# Teensy4-CANTool-Rev2.net
KiCad netlist of a schematic drawn in Altium Designer
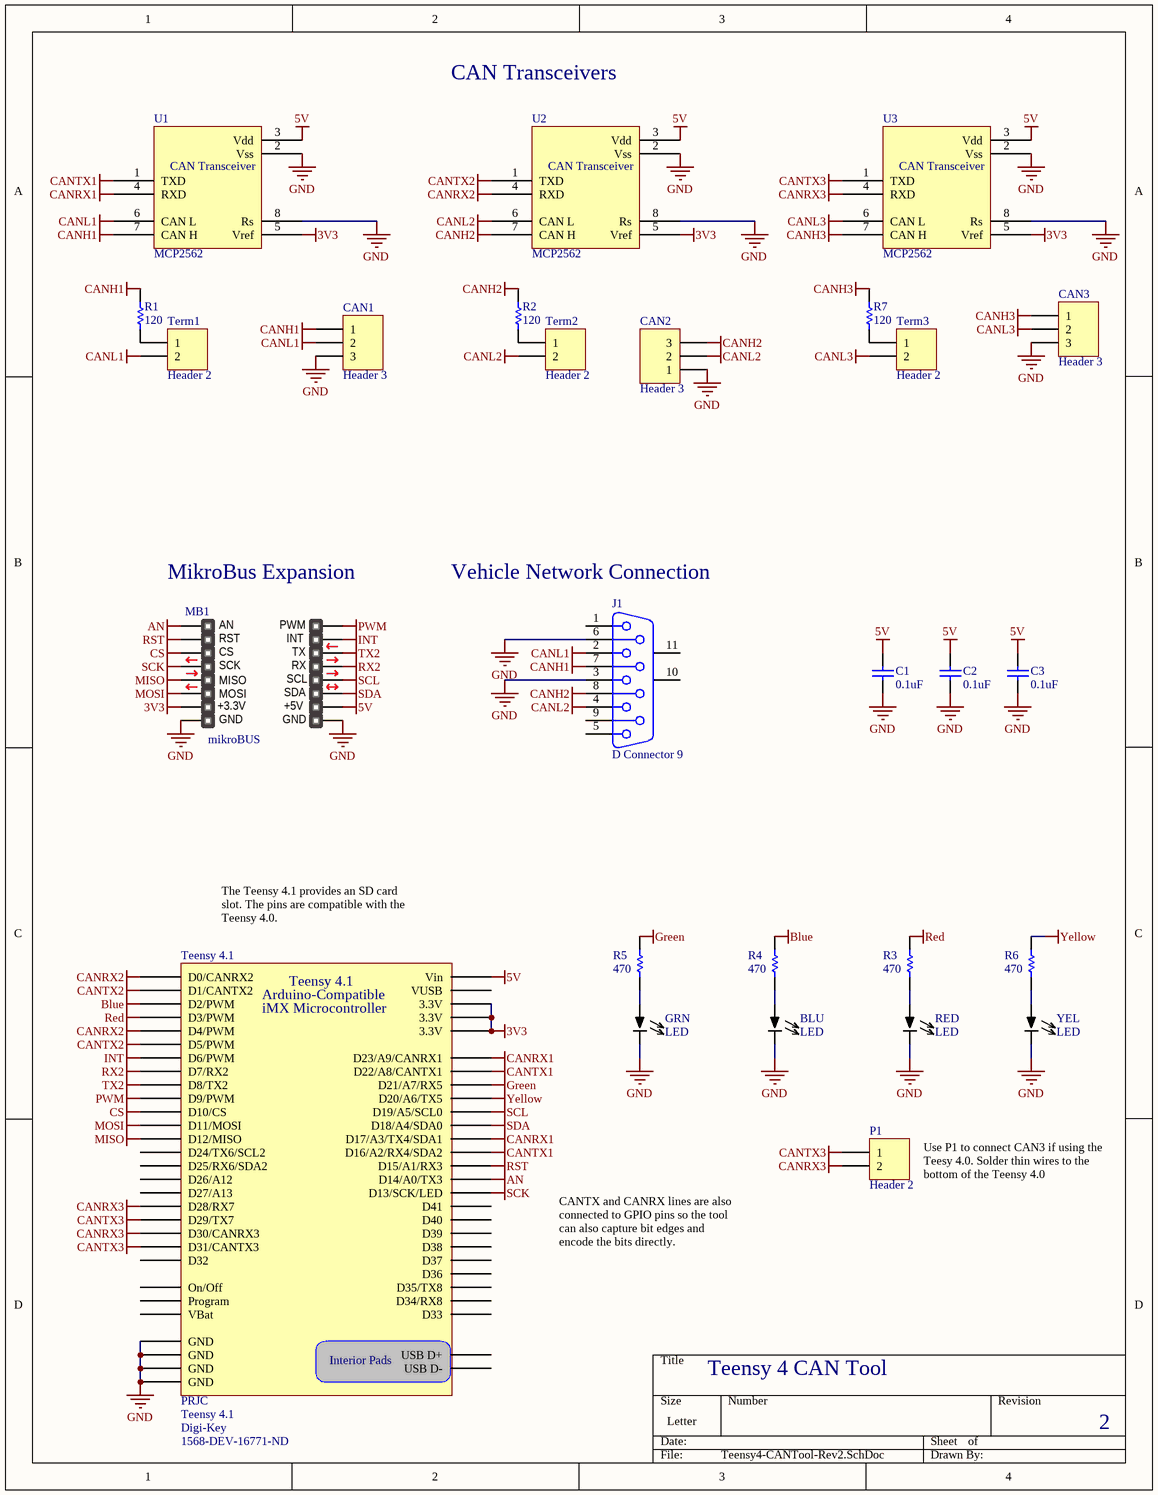
[diagram p0: Teensy4-CANTool-Rev2.SchDoc]

(export (version "E")
  (design (tool "Eeschema 10.0.6"))
  (components
    (comp (ref "BLU")
      (value "LED")
      (footprint "LED - 5mm Through Hole")
      (description "Blue 470nm LED Indication - Discrete 3.2V Radial")
      (fields (field (name "MANUFACTURER") "Würth Elektronik") (field (name "PARTNUMBER") "151051BS04000"))
      (libsource (lib "Custom Parts") (part "LED"))
    )
    (comp (ref "C1")
      (value "0.1uF")
      (footprint "CAPR5-4X5")
      (description "0.1µF ±10% 50V Ceramic Capacitor X7R 0603 (1608 Metric)")
      (fields
        (field (name "MANUFACTURER") "Vishay Beyschlag/Draloric/BC Components")
        (field (name "PARTNUMBER") "K104K15X7RF53H5")
      )
      (libsource (lib "SSS Schematic Library") (part "Cap"))
    )
    (comp (ref "C2")
      (value "0.1uF")
      (footprint "CAPR5-4X5")
      (description "0.1µF ±10% 50V Ceramic Capacitor X7R 0603 (1608 Metric)")
      (fields
        (field (name "MANUFACTURER") "Vishay Beyschlag/Draloric/BC Components")
        (field (name "PARTNUMBER") "K104K15X7RF53H5")
      )
      (libsource (lib "SSS Schematic Library") (part "Cap"))
    )
    (comp (ref "C3")
      (value "0.1uF")
      (footprint "CAPR5-4X5")
      (description "0.1µF ±10% 50V Ceramic Capacitor X7R 0603 (1608 Metric)")
      (fields
        (field (name "MANUFACTURER") "Vishay Beyschlag/Draloric/BC Components")
        (field (name "PARTNUMBER") "K104K15X7RF53H5")
      )
      (libsource (lib "SSS Schematic Library") (part "Cap"))
    )
    (comp (ref "CAN1")
      (value "Header 3")
      (footprint "PCB Terminal Block - 3")
      (description "Header, 3-Pin")
      (fields (field (name "MANUFACTURER") "Phoenix Contact") (field (name "PARTNUMBER") "1935174"))
      (libsource (lib "Miscellaneous Connectors") (part "Header 3"))
    )
    (comp (ref "CAN2")
      (value "Header 3")
      (footprint "PCB Terminal Block - 3")
      (description "Header, 3-Pin")
      (fields (field (name "MANUFACTURER") "Phoenix Contact") (field (name "PARTNUMBER") "1935174"))
      (libsource (lib "") (part "Header 3_1"))
    )
    (comp (ref "CAN3")
      (value "Header 3")
      (footprint "PCB Terminal Block - 3")
      (description "Header, 3-Pin")
      (fields (field (name "MANUFACTURER") "Phoenix Contact") (field (name "PARTNUMBER") "1935174"))
      (libsource (lib "Miscellaneous Connectors") (part "Header 3"))
    )
    (comp (ref "GRN")
      (value "LED")
      (footprint "LED - 5mm Through Hole")
      (description "Green 572nm LED Indication - Discrete 2.1V Radial")
      (fields (field (name "MANUFACTURER") "Würth Elektronik") (field (name "PARTNUMBER") "151051VS04000"))
      (libsource (lib "Custom Parts") (part "LED"))
    )
    (comp (ref "J1")
      (value "D Connector 9")
      (footprint "DSUB1.385-2H9")
      (description "CONN D-SUB PLUG 9POS R/A SLDR")
      (fields
        (field (name "MANUFACTURER") "Assmann WSW Components")
        (field (name "PARTNUMBER") "A-DS 09 A/KG-T2S")
      )
      (libsource (lib "Miscellaneous Connectors") (part "D Connector 9"))
    )
    (comp (ref "MB1")
      (value "mikroBUS")
      (footprint "mikroBUS - Midi")
      (description "mikroBUS compatible add-on board")
      (libsource (lib "mikroBUS_Add-on_standard") (part "mikroBUS compatible add-on board"))
    )
    (comp (ref "P1")
      (value "Header 2")
      (footprint "HDR1X2")
      (description "Header, 2-Pin")
      (libsource (lib "Miscellaneous Connectors") (part "Header 2"))
    )
    (comp (ref "R1")
      (value "120")
      (footprint "AXIAL-0.4")
      (description "120 Ohms ±5% 0.25W, 1/4W Through Hole Resistor Axial Carbon Film")
      (fields (field (name "MANUFACTURER") "YAGEO") (field (name "PARTNUMBER") "CFR-25JB-52-120R"))
      (libsource (lib "Miscellaneous Devices") (part "Res1"))
    )
    (comp (ref "R2")
      (value "120")
      (footprint "AXIAL-0.4")
      (description "120 Ohms ±5% 0.25W, 1/4W Through Hole Resistor Axial Carbon Film")
      (fields (field (name "MANUFACTURER") "YAGEO") (field (name "PARTNUMBER") "CFR-25JB-52-120R"))
      (libsource (lib "Miscellaneous Devices") (part "Res1"))
    )
    (comp (ref "R3")
      (value "470")
      (footprint "AXIAL-0.4")
      (description "470 Ohms ±5% 0.25W, 1/4W Through Hole Resistor Axial Carbon Film")
      (fields (field (name "MANUFACTURER") "YAGEO") (field (name "PARTNUMBER") "CFR-25JB-52-470R"))
      (libsource (lib "Miscellaneous Devices") (part "Res1"))
    )
    (comp (ref "R4")
      (value "470")
      (footprint "AXIAL-0.4")
      (description "470 Ohms ±5% 0.25W, 1/4W Through Hole Resistor Axial Carbon Film")
      (fields (field (name "MANUFACTURER") "YAGEO") (field (name "PARTNUMBER") "CFR-25JB-52-470R"))
      (libsource (lib "Miscellaneous Devices") (part "Res1"))
    )
    (comp (ref "R5")
      (value "470")
      (footprint "AXIAL-0.4")
      (description "470 Ohms ±5% 0.25W, 1/4W Through Hole Resistor Axial Carbon Film")
      (fields (field (name "MANUFACTURER") "YAGEO") (field (name "PARTNUMBER") "CFR-25JB-52-470R"))
      (libsource (lib "Miscellaneous Devices") (part "Res1"))
    )
    (comp (ref "R6")
      (value "470")
      (footprint "AXIAL-0.4")
      (description "470 Ohms ±5% 0.25W, 1/4W Through Hole Resistor Axial Carbon Film")
      (fields (field (name "MANUFACTURER") "YAGEO") (field (name "PARTNUMBER") "CFR-25JB-52-470R"))
      (libsource (lib "Miscellaneous Devices") (part "Res1"))
    )
    (comp (ref "R7")
      (value "120")
      (footprint "AXIAL-0.4")
      (description "120 Ohms ±5% 0.25W, 1/4W Through Hole Resistor Axial Carbon Film")
      (fields (field (name "MANUFACTURER") "YAGEO") (field (name "PARTNUMBER") "CFR-25JB-52-120R"))
      (libsource (lib "Miscellaneous Devices") (part "Res1"))
    )
    (comp (ref "RED")
      (value "LED")
      (footprint "LED - 5mm Through Hole")
      (description "Red 645nm LED Indication - Discrete 2.1V Radial")
      (fields (field (name "MANUFACTURER") "Würth Elektronik") (field (name "PARTNUMBER") "151051RS11000"))
      (libsource (lib "Custom Parts") (part "LED"))
    )
    (comp (ref "Teensy 4.1")
      (value "Teensy 4.1")
      (footprint "Teensy 4.1")
      (description "32 Bit Arduino-Compatible iMX Microcontroller")
      (fields
        (field (name "MANUFACTURER") "PRJC")
        (field (name "PARTNUMBER") "Teensy 4.1")
        (field (name "SUPPLIER 1") "Digi-Key")
        (field (name "SUPPLIER PART NUMBER 1") "1568-DEV-16771-ND")
      )
      (libsource (lib "Teensy") (part "Teensy 4.1"))
    )
    (comp (ref "Term1")
      (value "Header 2")
      (footprint "HDR1X2")
      (description "2 (1 x 2) Position Shunt Connector Open Top, Grip 0.100\" (2.54mm) Gold")
      (fields
        (field (name "MANUFACTURER") "Sullins Connector Solutions")
        (field (name "PARTNUMBER") "NPC02SXON-RC")
      )
      (libsource (lib "Miscellaneous Connectors") (part "Header 2"))
    )
    (comp (ref "Term2")
      (value "Header 2")
      (footprint "HDR1X2")
      (description "2 (1 x 2) Position Shunt Connector Open Top, Grip 0.100\" (2.54mm) Gold")
      (fields
        (field (name "MANUFACTURER") "Sullins Connector Solutions")
        (field (name "PARTNUMBER") "NPC02SXON-RC")
      )
      (libsource (lib "Miscellaneous Connectors") (part "Header 2"))
    )
    (comp (ref "Term3")
      (value "Header 2")
      (footprint "HDR1X2")
      (description "2 (1 x 2) Position Shunt Connector Open Top, Grip 0.100\" (2.54mm) Gold")
      (fields
        (field (name "MANUFACTURER") "Sullins Connector Solutions")
        (field (name "PARTNUMBER") "NPC02SXON-RC")
      )
      (libsource (lib "Miscellaneous Connectors") (part "Header 2"))
    )
    (comp (ref "U1")
      (value "MCP2562")
      (footprint "DIP8")
      (description "1/1 Transceiver CANbus 8-PDIP")
      (fields
        (field (name "MANUFACTURER") "Microchip Technology")
        (field (name "PARTNUMBER") "MCP2562FD-E/P")
      )
      (libsource (lib "SSS Integrated Library") (part "MCP2551"))
    )
    (comp (ref "U2")
      (value "MCP2562")
      (footprint "DIP8")
      (description "1/1 Transceiver CANbus 8-PDIP")
      (fields
        (field (name "MANUFACTURER") "Microchip Technology")
        (field (name "PARTNUMBER") "MCP2562FD-E/P")
      )
      (libsource (lib "SSS Integrated Library") (part "MCP2551"))
    )
    (comp (ref "U3")
      (value "MCP2562")
      (footprint "DIP8")
      (description "1/1 Transceiver CANbus 8-PDIP")
      (fields
        (field (name "MANUFACTURER") "Microchip Technology")
        (field (name "PARTNUMBER") "MCP2562FD-E/P")
      )
      (libsource (lib "SSS Integrated Library") (part "MCP2551"))
    )
    (comp (ref "YEL")
      (value "LED")
      (footprint "LED - 5mm Through Hole")
      (description "Yellow 590nm LED Indication - Discrete 2V Radial")
      (fields (field (name "MANUFACTURER") "Würth Elektronik") (field (name "PARTNUMBER") "151051YS04000"))
      (libsource (lib "Custom Parts") (part "LED"))
    )
  )
  (nets
    (net (code "1") (name "3V3") (class "Default")
      (node (ref "MB1") (pin "7") (pinfunction "3.3V_7") (pintype "passive"))
      (node (ref "Teensy 4.1") (pin "3V3a") (pinfunction "3.3V_3V3a") (pintype "passive"))
      (node (ref "Teensy 4.1") (pin "3V3b") (pinfunction "3.3V_3V3b") (pintype "passive"))
      (node (ref "Teensy 4.1") (pin "3V3c") (pinfunction "3.3V_3V3c") (pintype "passive"))
      (node (ref "U1") (pin "5") (pinfunction "Vref_5") (pintype "passive"))
      (node (ref "U2") (pin "5") (pinfunction "Vref_5") (pintype "passive"))
      (node (ref "U3") (pin "5") (pinfunction "Vref_5") (pintype "passive"))
    )
    (net (code "2") (name "5V") (class "Default")
      (node (ref "C1") (pin "2") (pinfunction "2_2") (pintype "passive"))
      (node (ref "C2") (pin "2") (pinfunction "2_2") (pintype "passive"))
      (node (ref "C3") (pin "2") (pinfunction "2_2") (pintype "passive"))
      (node (ref "MB1") (pin "10") (pinfunction "5V_10") (pintype "passive"))
      (node (ref "Teensy 4.1") (pin "Vin") (pinfunction "Vin_Vin") (pintype "passive"))
      (node (ref "U1") (pin "3") (pinfunction "Vdd_3") (pintype "passive"))
      (node (ref "U2") (pin "3") (pinfunction "Vdd_3") (pintype "passive"))
      (node (ref "U3") (pin "3") (pinfunction "Vdd_3") (pintype "passive"))
    )
    (net (code "3") (name "AN") (class "Default")
      (node (ref "MB1") (pin "1") (pinfunction "AN_1") (pintype "passive"))
      (node (ref "Teensy 4.1") (pin "14") (pinfunction "D14/A0/TX3_14") (pintype "passive"))
    )
    (net (code "4") (name "Blue") (class "Default")
      (node (ref "R4") (pin "2") (pinfunction "2_2") (pintype "passive"))
      (node (ref "Teensy 4.1") (pin "2") (pinfunction "D2/PWM_2") (pintype "passive"))
    )
    (net (code "5") (name "CANH1") (class "Default")
      (node (ref "CAN1") (pin "1") (pinfunction "1_1") (pintype "passive"))
      (node (ref "J1") (pin "7") (pinfunction "7_7") (pintype "passive"))
      (node (ref "R1") (pin "1") (pinfunction "1_1") (pintype "passive"))
      (node (ref "U1") (pin "7") (pinfunction "CAN_H_7") (pintype "passive"))
    )
    (net (code "6") (name "CANH2") (class "Default")
      (node (ref "CAN2") (pin "3") (pinfunction "3_3") (pintype "passive"))
      (node (ref "J1") (pin "8") (pinfunction "8_8") (pintype "passive"))
      (node (ref "R2") (pin "1") (pinfunction "1_1") (pintype "passive"))
      (node (ref "U2") (pin "7") (pinfunction "CAN_H_7") (pintype "passive"))
    )
    (net (code "7") (name "CANH3") (class "Default")
      (node (ref "CAN3") (pin "1") (pinfunction "1_1") (pintype "passive"))
      (node (ref "R7") (pin "1") (pinfunction "1_1") (pintype "passive"))
      (node (ref "U3") (pin "7") (pinfunction "CAN_H_7") (pintype "passive"))
    )
    (net (code "8") (name "CANL1") (class "Default")
      (node (ref "CAN1") (pin "2") (pinfunction "2_2") (pintype "passive"))
      (node (ref "J1") (pin "2") (pinfunction "2_2") (pintype "passive"))
      (node (ref "Term1") (pin "2") (pinfunction "2_2") (pintype "passive"))
      (node (ref "U1") (pin "6") (pinfunction "CAN_L_6") (pintype "passive"))
    )
    (net (code "9") (name "CANL2") (class "Default")
      (node (ref "CAN2") (pin "2") (pinfunction "2_2") (pintype "passive"))
      (node (ref "J1") (pin "4") (pinfunction "4_4") (pintype "passive"))
      (node (ref "Term2") (pin "2") (pinfunction "2_2") (pintype "passive"))
      (node (ref "U2") (pin "6") (pinfunction "CAN_L_6") (pintype "passive"))
    )
    (net (code "10") (name "CANL3") (class "Default")
      (node (ref "CAN3") (pin "2") (pinfunction "2_2") (pintype "passive"))
      (node (ref "Term3") (pin "2") (pinfunction "2_2") (pintype "passive"))
      (node (ref "U3") (pin "6") (pinfunction "CAN_L_6") (pintype "passive"))
    )
    (net (code "11") (name "CANRX1") (class "Default")
      (node (ref "Teensy 4.1") (pin "17") (pinfunction "D17/A3/TX4/SDA1_17") (pintype "passive"))
      (node (ref "Teensy 4.1") (pin "23") (pinfunction "D23/A9/CANRX1_23") (pintype "passive"))
      (node (ref "U1") (pin "4") (pinfunction "RXD_4") (pintype "passive"))
    )
    (net (code "12") (name "CANRX2") (class "Default")
      (node (ref "Teensy 4.1") (pin "0") (pinfunction "D0/CANRX2_0") (pintype "passive"))
      (node (ref "Teensy 4.1") (pin "4") (pinfunction "D4/PWM_4") (pintype "passive"))
      (node (ref "U2") (pin "4") (pinfunction "RXD_4") (pintype "passive"))
    )
    (net (code "13") (name "CANRX3") (class "Default")
      (node (ref "P1") (pin "2") (pinfunction "2_2") (pintype "passive"))
      (node (ref "Teensy 4.1") (pin "28") (pinfunction "D28/RX7_28") (pintype "passive"))
      (node (ref "Teensy 4.1") (pin "30") (pinfunction "D30/CANRX3_30") (pintype "passive"))
      (node (ref "U3") (pin "4") (pinfunction "RXD_4") (pintype "passive"))
    )
    (net (code "14") (name "CANTX1") (class "Default")
      (node (ref "Teensy 4.1") (pin "16") (pinfunction "D16/A2/RX4/SDA2_16") (pintype "passive"))
      (node (ref "Teensy 4.1") (pin "22") (pinfunction "D22/A8/CANTX1_22") (pintype "passive"))
      (node (ref "U1") (pin "1") (pinfunction "TXD_1") (pintype "passive"))
    )
    (net (code "15") (name "CANTX2") (class "Default")
      (node (ref "Teensy 4.1") (pin "1") (pinfunction "D1/CANTX2_1") (pintype "passive"))
      (node (ref "Teensy 4.1") (pin "5") (pinfunction "D5/PWM_5") (pintype "passive"))
      (node (ref "U2") (pin "1") (pinfunction "TXD_1") (pintype "passive"))
    )
    (net (code "16") (name "CANTX3") (class "Default")
      (node (ref "P1") (pin "1") (pinfunction "1_1") (pintype "passive"))
      (node (ref "Teensy 4.1") (pin "29") (pinfunction "D29/TX7_29") (pintype "passive"))
      (node (ref "Teensy 4.1") (pin "31") (pinfunction "D31/CANTX3_31") (pintype "passive"))
      (node (ref "U3") (pin "1") (pinfunction "TXD_1") (pintype "passive"))
    )
    (net (code "17") (name "CS") (class "Default")
      (node (ref "MB1") (pin "3") (pinfunction "CS_3") (pintype "passive"))
      (node (ref "Teensy 4.1") (pin "10") (pinfunction "D10/CS_10") (pintype "passive"))
    )
    (net (code "18") (name "GND") (class "Default")
      (node (ref "BLU") (pin "2") (pinfunction "C_2") (pintype "passive"))
      (node (ref "C1") (pin "1") (pinfunction "1_1") (pintype "passive"))
      (node (ref "C2") (pin "1") (pinfunction "1_1") (pintype "passive"))
      (node (ref "C3") (pin "1") (pinfunction "1_1") (pintype "passive"))
      (node (ref "CAN1") (pin "3") (pinfunction "3_3") (pintype "passive"))
      (node (ref "CAN2") (pin "1") (pinfunction "1_1") (pintype "passive"))
      (node (ref "CAN3") (pin "3") (pinfunction "3_3") (pintype "passive"))
      (node (ref "GRN") (pin "2") (pinfunction "C_2") (pintype "passive"))
      (node (ref "J1") (pin "3") (pinfunction "3_3") (pintype "passive"))
      (node (ref "J1") (pin "6") (pinfunction "6_6") (pintype "passive"))
      (node (ref "MB1") (pin "8") (pinfunction "GND_8") (pintype "passive"))
      (node (ref "MB1") (pin "9") (pinfunction "GND_9") (pintype "passive"))
      (node (ref "RED") (pin "2") (pinfunction "C_2") (pintype "passive"))
      (node (ref "Teensy 4.1") (pin "G1") (pinfunction "GND_G1") (pintype "passive"))
      (node (ref "Teensy 4.1") (pin "G2") (pinfunction "GND_G2") (pintype "passive"))
      (node (ref "Teensy 4.1") (pin "G3") (pinfunction "GND_G3") (pintype "passive"))
      (node (ref "Teensy 4.1") (pin "G4") (pinfunction "GND_G4") (pintype "passive"))
      (node (ref "U1") (pin "2") (pinfunction "Vss_2") (pintype "passive"))
      (node (ref "U1") (pin "8") (pinfunction "Rs_8") (pintype "passive"))
      (node (ref "U2") (pin "2") (pinfunction "Vss_2") (pintype "passive"))
      (node (ref "U2") (pin "8") (pinfunction "Rs_8") (pintype "passive"))
      (node (ref "U3") (pin "2") (pinfunction "Vss_2") (pintype "passive"))
      (node (ref "U3") (pin "8") (pinfunction "Rs_8") (pintype "passive"))
      (node (ref "YEL") (pin "2") (pinfunction "C_2") (pintype "passive"))
    )
    (net (code "19") (name "Green") (class "Default")
      (node (ref "R5") (pin "2") (pinfunction "2_2") (pintype "passive"))
      (node (ref "Teensy 4.1") (pin "21") (pinfunction "D21/A7/RX5_21") (pintype "passive"))
    )
    (net (code "20") (name "INT") (class "Default")
      (node (ref "MB1") (pin "15") (pinfunction "INT_15") (pintype "passive"))
      (node (ref "Teensy 4.1") (pin "6") (pinfunction "D6/PWM_6") (pintype "passive"))
    )
    (net (code "21") (name "MISO") (class "Default")
      (node (ref "MB1") (pin "5") (pinfunction "MISO_5") (pintype "passive"))
      (node (ref "Teensy 4.1") (pin "12") (pinfunction "D12/MISO_12") (pintype "passive"))
    )
    (net (code "22") (name "MOSI") (class "Default")
      (node (ref "MB1") (pin "6") (pinfunction "MOSI_6") (pintype "passive"))
      (node (ref "Teensy 4.1") (pin "11") (pinfunction "D11/MOSI_11") (pintype "passive"))
    )
    (net (code "23") (name "Net-(BLU-A)") (class "Default")
      (node (ref "BLU") (pin "1") (pinfunction "A_1") (pintype "passive"))
      (node (ref "R4") (pin "1") (pinfunction "1_1") (pintype "passive"))
    )
    (net (code "24") (name "Net-(GRN-A)") (class "Default")
      (node (ref "GRN") (pin "1") (pinfunction "A_1") (pintype "passive"))
      (node (ref "R5") (pin "1") (pinfunction "1_1") (pintype "passive"))
    )
    (net (code "25") (name "Net-(R1-Pad2)") (class "Default")
      (node (ref "R1") (pin "2") (pinfunction "2_2") (pintype "passive"))
      (node (ref "Term1") (pin "1") (pinfunction "1_1") (pintype "passive"))
    )
    (net (code "26") (name "Net-(R2-Pad2)") (class "Default")
      (node (ref "R2") (pin "2") (pinfunction "2_2") (pintype "passive"))
      (node (ref "Term2") (pin "1") (pinfunction "1_1") (pintype "passive"))
    )
    (net (code "27") (name "Net-(R7-Pad2)") (class "Default")
      (node (ref "R7") (pin "2") (pinfunction "2_2") (pintype "passive"))
      (node (ref "Term3") (pin "1") (pinfunction "1_1") (pintype "passive"))
    )
    (net (code "28") (name "Net-(RED-A)") (class "Default")
      (node (ref "R3") (pin "1") (pinfunction "1_1") (pintype "passive"))
      (node (ref "RED") (pin "1") (pinfunction "A_1") (pintype "passive"))
    )
    (net (code "29") (name "Net-(YEL-A)") (class "Default")
      (node (ref "R6") (pin "1") (pinfunction "1_1") (pintype "passive"))
      (node (ref "YEL") (pin "1") (pinfunction "A_1") (pintype "passive"))
    )
    (net (code "30") (name "PWM") (class "Default")
      (node (ref "MB1") (pin "16") (pinfunction "PWM_16") (pintype "passive"))
      (node (ref "Teensy 4.1") (pin "9") (pinfunction "D9/PWM_9") (pintype "passive"))
    )
    (net (code "31") (name "RST") (class "Default")
      (node (ref "MB1") (pin "2") (pinfunction "RST_2") (pintype "passive"))
      (node (ref "Teensy 4.1") (pin "15") (pinfunction "D15/A1/RX3_15") (pintype "passive"))
    )
    (net (code "32") (name "RX2") (class "Default")
      (node (ref "MB1") (pin "13") (pinfunction "TX_13") (pintype "passive"))
      (node (ref "Teensy 4.1") (pin "7") (pinfunction "D7/RX2_7") (pintype "passive"))
    )
    (net (code "33") (name "Red") (class "Default")
      (node (ref "R3") (pin "2") (pinfunction "2_2") (pintype "passive"))
      (node (ref "Teensy 4.1") (pin "3") (pinfunction "D3/PWM_3") (pintype "passive"))
    )
    (net (code "34") (name "SCK") (class "Default")
      (node (ref "MB1") (pin "4") (pinfunction "SCK_4") (pintype "passive"))
      (node (ref "Teensy 4.1") (pin "13") (pinfunction "D13/SCK/LED_13") (pintype "passive"))
    )
    (net (code "35") (name "SCL") (class "Default")
      (node (ref "MB1") (pin "12") (pinfunction "SCL_12") (pintype "passive"))
      (node (ref "Teensy 4.1") (pin "19") (pinfunction "D19/A5/SCL0_19") (pintype "passive"))
    )
    (net (code "36") (name "SDA") (class "Default")
      (node (ref "MB1") (pin "11") (pinfunction "SDA_11") (pintype "passive"))
      (node (ref "Teensy 4.1") (pin "18") (pinfunction "D18/A4/SDA0_18") (pintype "passive"))
    )
    (net (code "37") (name "TX2") (class "Default")
      (node (ref "MB1") (pin "14") (pinfunction "RX_14") (pintype "passive"))
      (node (ref "Teensy 4.1") (pin "8") (pinfunction "D8/TX2_8") (pintype "passive"))
    )
    (net (code "38") (name "Yellow") (class "Default")
      (node (ref "R6") (pin "2") (pinfunction "2_2") (pintype "passive"))
      (node (ref "Teensy 4.1") (pin "20") (pinfunction "D20/A6/TX5_20") (pintype "passive"))
    )
    (net (code "39") (name "unconnected-(J1-MH1-Pad10)") (class "Default")
      (node (ref "J1") (pin "10") (pinfunction "MH1_10") (pintype "passive"))
    )
    (net (code "40") (name "unconnected-(J1-MH2-Pad11)") (class "Default")
      (node (ref "J1") (pin "11") (pinfunction "MH2_11") (pintype "passive"))
    )
    (net (code "41") (name "unconnected-(J1-Pad1)") (class "Default")
      (node (ref "J1") (pin "1") (pinfunction "1_1") (pintype "passive"))
    )
    (net (code "42") (name "unconnected-(J1-Pad5)") (class "Default")
      (node (ref "J1") (pin "5") (pinfunction "5_5") (pintype "passive"))
    )
    (net (code "43") (name "unconnected-(J1-Pad9)") (class "Default")
      (node (ref "J1") (pin "9") (pinfunction "9_9") (pintype "passive"))
    )
    (net (code "44") (name "unconnected-(Teensy 4.1-D24{slash}TX6{slash}SCL2-Pad24)") (class "Default")
      (node (ref "Teensy 4.1") (pin "24") (pinfunction "D24/TX6/SCL2_24") (pintype "passive"))
    )
    (net (code "45") (name "unconnected-(Teensy 4.1-D25{slash}RX6{slash}SDA2-Pad25)") (class "Default")
      (node (ref "Teensy 4.1") (pin "25") (pinfunction "D25/RX6/SDA2_25") (pintype "passive"))
    )
    (net (code "46") (name "unconnected-(Teensy 4.1-D26{slash}A12-Pad26)") (class "Default")
      (node (ref "Teensy 4.1") (pin "26") (pinfunction "D26/A12_26") (pintype "passive"))
    )
    (net (code "47") (name "unconnected-(Teensy 4.1-D27{slash}A13-Pad27)") (class "Default")
      (node (ref "Teensy 4.1") (pin "27") (pinfunction "D27/A13_27") (pintype "passive"))
    )
    (net (code "48") (name "unconnected-(Teensy 4.1-D32-Pad32)") (class "Default")
      (node (ref "Teensy 4.1") (pin "32") (pinfunction "D32_32") (pintype "passive"))
    )
    (net (code "49") (name "unconnected-(Teensy 4.1-D33-Pad33)") (class "Default")
      (node (ref "Teensy 4.1") (pin "33") (pinfunction "D33_33") (pintype "passive"))
    )
    (net (code "50") (name "unconnected-(Teensy 4.1-D34{slash}RX8-Pad34)") (class "Default")
      (node (ref "Teensy 4.1") (pin "34") (pinfunction "D34/RX8_34") (pintype "passive"))
    )
    (net (code "51") (name "unconnected-(Teensy 4.1-D35{slash}TX8-Pad35)") (class "Default")
      (node (ref "Teensy 4.1") (pin "35") (pinfunction "D35/TX8_35") (pintype "passive"))
    )
    (net (code "52") (name "unconnected-(Teensy 4.1-D36-Pad36)") (class "Default")
      (node (ref "Teensy 4.1") (pin "36") (pinfunction "D36_36") (pintype "passive"))
    )
    (net (code "53") (name "unconnected-(Teensy 4.1-D37-Pad37)") (class "Default")
      (node (ref "Teensy 4.1") (pin "37") (pinfunction "D37_37") (pintype "passive"))
    )
    (net (code "54") (name "unconnected-(Teensy 4.1-D38-Pad38)") (class "Default")
      (node (ref "Teensy 4.1") (pin "38") (pinfunction "D38_38") (pintype "passive"))
    )
    (net (code "55") (name "unconnected-(Teensy 4.1-D39-Pad39)") (class "Default")
      (node (ref "Teensy 4.1") (pin "39") (pinfunction "D39_39") (pintype "passive"))
    )
    (net (code "56") (name "unconnected-(Teensy 4.1-D40-Pad40)") (class "Default")
      (node (ref "Teensy 4.1") (pin "40") (pinfunction "D40_40") (pintype "passive"))
    )
    (net (code "57") (name "unconnected-(Teensy 4.1-D41-Pad41)") (class "Default")
      (node (ref "Teensy 4.1") (pin "41") (pinfunction "D41_41") (pintype "passive"))
    )
    (net (code "58") (name "unconnected-(Teensy 4.1-On{slash}Off-PadOn)") (class "Default")
      (node (ref "Teensy 4.1") (pin "On") (pinfunction "On/Off_On") (pintype "passive"))
    )
    (net (code "59") (name "unconnected-(Teensy 4.1-PadVBat)") (class "Default")
      (node (ref "Teensy 4.1") (pin "VBat") (pinfunction "VBat_VBat") (pintype "passive"))
    )
    (net (code "60") (name "unconnected-(Teensy 4.1-PadVUSB)") (class "Default")
      (node (ref "Teensy 4.1") (pin "VUSB") (pinfunction "VUSB_VUSB") (pintype "passive"))
    )
    (net (code "61") (name "unconnected-(Teensy 4.1-Program-PadP)") (class "Default")
      (node (ref "Teensy 4.1") (pin "P") (pinfunction "Program_P") (pintype "passive"))
    )
    (net (code "62") (name "unconnected-(Teensy 4.1-USB_D+-PadD+)") (class "Default")
      (node (ref "Teensy 4.1") (pin "D+") (pinfunction "USB_D+_D+") (pintype "passive"))
    )
    (net (code "63") (name "unconnected-(Teensy 4.1-USB_D--PadD-)") (class "Default")
      (node (ref "Teensy 4.1") (pin "D-") (pinfunction "USB_D-_D-") (pintype "passive"))
    )
  )
)
